# BLE.net
KiCad netlist of a schematic drawn in Altium Designer
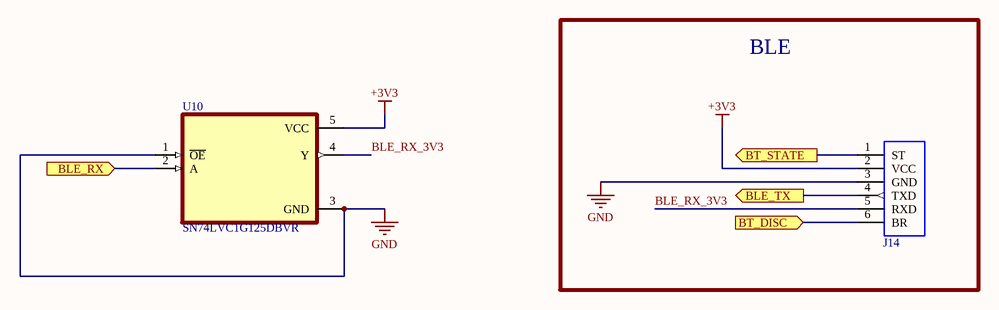
[diagram p0: BLE.SchDoc]

(export (version "E")
  (design (tool "Eeschema 10.0.6"))
  (components
    (comp (ref "J14")
      (value "61300611821")
      (footprint "HM-10_BLE_MODULE")
      (description "WR-PHD Socket Header, THT, Vertical, pitch 2.54mm, 1 Row, 6P")
      (fields (field (name "MANUFACTURER") "Wurth Elektronik"))
      (libsource (lib "TAREKPCBLIB") (part "HM-10_BLE_MODULE"))
    )
    (comp (ref "U10")
      (value "SN74LVC1G125DBVR")
      (footprint "SOT95P280X145-5N")
      (description "Single Bus Buffer Gate With 3-State Outputs 5-SOT-23 -40 to 125")
      (fields (field (name "MF") "Texas Instruments"))
      (libsource (lib "TAREKPCBLIB") (part "SN74LVC1G125DBVR"))
    )
  )
  (nets
    (net (code "1") (name "+3V3") (class "Default")
      (node (ref "J14") (pin "2") (pinfunction "VCC_2") (pintype "passive"))
      (node (ref "U10") (pin "5") (pinfunction "VCC_5") (pintype "power_in"))
    )
    (net (code "2") (name "/BLE_RX") (class "Default")
      (node (ref "U10") (pin "2") (pinfunction "A_2") (pintype "input"))
    )
    (net (code "3") (name "/BLE_RX_3V3") (class "Default")
      (node (ref "J14") (pin "5") (pinfunction "RXD_5") (pintype "passive"))
      (node (ref "U10") (pin "4") (pinfunction "Y_4") (pintype "output"))
    )
    (net (code "4") (name "/BLE_TX") (class "Default")
      (node (ref "J14") (pin "4") (pinfunction "TXD_4") (pintype "output"))
    )
    (net (code "5") (name "/BT_DISC") (class "Default")
      (node (ref "J14") (pin "6") (pinfunction "BR_6") (pintype "passive"))
    )
    (net (code "6") (name "/BT_STATE") (class "Default")
      (node (ref "J14") (pin "1") (pinfunction "ST_1") (pintype "passive"))
    )
    (net (code "7") (name "GND") (class "Default")
      (node (ref "J14") (pin "3") (pinfunction "GND_3") (pintype "passive"))
      (node (ref "U10") (pin "1") (pinfunction "~{OE}_1") (pintype "input"))
      (node (ref "U10") (pin "3") (pinfunction "GND_3") (pintype "power_in"))
    )
  )
)
